# firefly-light.net
KiCad netlist of a schematic drawn in EAGLE
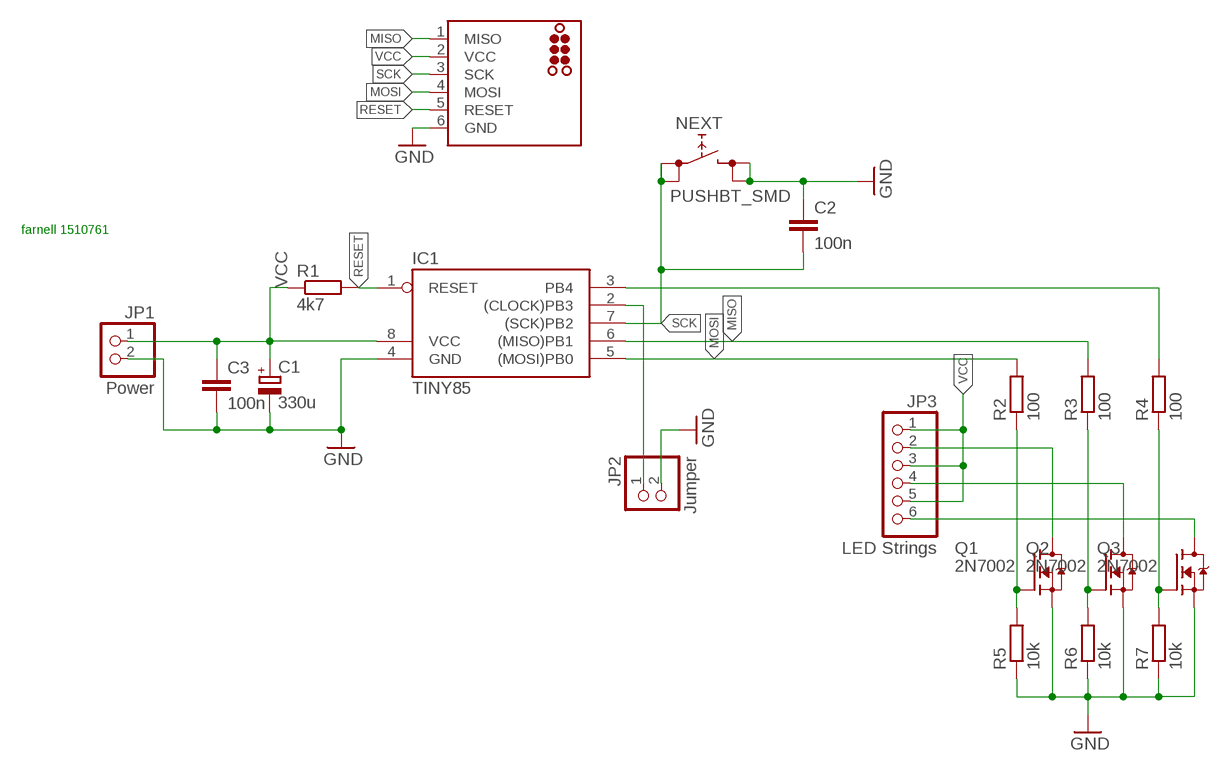
[diagram p0: schematic, sheet 1]

(export (version "E")
  (design (tool "Eeschema 10.0.6"))
  (components
    (comp (ref "C1")
      (value "330u")
      (footprint "eagle-import:E3,5-8")
      (libsource (lib "eagle-import") (part "CPOL-EUE3.5-8"))
    )
    (comp (ref "C2")
      (value "100n")
      (footprint "eagle-import:C0805")
      (libsource (lib "eagle-import") (part "C-EUC0805"))
    )
    (comp (ref "C3")
      (value "100n")
      (footprint "eagle-import:C0805")
      (libsource (lib "eagle-import") (part "C-EUC0805"))
    )
    (comp (ref "IC1")
      (value "TINY85")
      (footprint "eagle-import:SOIC8")
      (libsource (lib "eagle-import") (part "TINY22S"))
    )
    (comp (ref "ISP")
      (value "TC2030-MCP-NL")
      (footprint "eagle-import:TC2030-MCP-NL")
      (libsource (lib "eagle-import") (part "TC2030-MCP-NL"))
    )
    (comp (ref "JP1")
      (value "Power")
      (footprint "eagle-import:1X02")
      (libsource (lib "eagle-import") (part "PINHD-1X2"))
    )
    (comp (ref "JP2")
      (value "Jumper")
      (footprint "eagle-import:1X02")
      (libsource (lib "eagle-import") (part "PINHD-1X2"))
    )
    (comp (ref "JP3")
      (value "LED Strings")
      (footprint "eagle-import:1X06")
      (libsource (lib "eagle-import") (part "PINHD-1X6"))
    )
    (comp (ref "NEXT")
      (value "PUSHBT_SMD")
      (footprint "eagle-import:PUSHBUTTON")
      (libsource (lib "eagle-import") (part "PUSHBT_SMD"))
    )
    (comp (ref "Q1")
      (value "2N7002")
      (footprint "eagle-import:SOT-23")
      (libsource (lib "eagle-import") (part "2N7002"))
    )
    (comp (ref "Q2")
      (value "2N7002")
      (footprint "eagle-import:SOT-23")
      (libsource (lib "eagle-import") (part "2N7002"))
    )
    (comp (ref "Q3")
      (value "2N7002")
      (footprint "eagle-import:SOT-23")
      (libsource (lib "eagle-import") (part "2N7002"))
    )
    (comp (ref "R1")
      (value "4k7")
      (footprint "eagle-import:R0805")
      (libsource (lib "eagle-import") (part "R-EU_R0805"))
    )
    (comp (ref "R2")
      (value "100")
      (footprint "eagle-import:R0805")
      (libsource (lib "eagle-import") (part "R-EU_R0805"))
    )
    (comp (ref "R3")
      (value "100")
      (footprint "eagle-import:R0805")
      (libsource (lib "eagle-import") (part "R-EU_R0805"))
    )
    (comp (ref "R4")
      (value "100")
      (footprint "eagle-import:R0805")
      (libsource (lib "eagle-import") (part "R-EU_R0805"))
    )
    (comp (ref "R5")
      (value "10k")
      (footprint "eagle-import:R0805")
      (libsource (lib "eagle-import") (part "R-EU_R0805"))
    )
    (comp (ref "R6")
      (value "10k")
      (footprint "eagle-import:R0805")
      (libsource (lib "eagle-import") (part "R-EU_R0805"))
    )
    (comp (ref "R7")
      (value "10k")
      (footprint "eagle-import:R0805")
      (libsource (lib "eagle-import") (part "R-EU_R0805"))
    )
  )
  (nets
    (net (code "1") (name "GND") (class "Default")
      (node (ref "C1") (pin "-") (pinfunction "-_-") (pintype "passive"))
      (node (ref "C2") (pin "1") (pinfunction "1_1") (pintype "passive"))
      (node (ref "C3") (pin "2") (pinfunction "2_2") (pintype "passive"))
      (node (ref "IC1") (pin "4") (pinfunction "GND_4") (pintype "power_in"))
      (node (ref "ISP") (pin "6") (pinfunction "GND_6") (pintype "power_in"))
      (node (ref "JP1") (pin "2") (pinfunction "2_2") (pintype "passive"))
      (node (ref "JP2") (pin "2") (pinfunction "2_2") (pintype "passive"))
      (node (ref "NEXT") (pin "B1") (pinfunction "1_B1") (pintype "passive"))
      (node (ref "NEXT") (pin "B2") (pinfunction "1_B2") (pintype "passive"))
      (node (ref "Q1") (pin "2") (pinfunction "S_2") (pintype "passive"))
      (node (ref "Q2") (pin "2") (pinfunction "S_2") (pintype "passive"))
      (node (ref "Q3") (pin "2") (pinfunction "S_2") (pintype "passive"))
      (node (ref "R5") (pin "1") (pinfunction "1_1") (pintype "passive"))
      (node (ref "R6") (pin "1") (pinfunction "1_1") (pintype "passive"))
      (node (ref "R7") (pin "1") (pinfunction "1_1") (pintype "passive"))
    )
    (net (code "2") (name "MISO") (class "Default")
      (node (ref "IC1") (pin "6") (pinfunction "(MISO)PB1_6") (pintype "bidirectional"))
      (node (ref "ISP") (pin "1") (pinfunction "MISO_1") (pintype "input"))
      (node (ref "R3") (pin "2") (pinfunction "2_2") (pintype "passive"))
    )
    (net (code "3") (name "MOSI") (class "Default")
      (node (ref "IC1") (pin "5") (pinfunction "(MOSI)PB0_5") (pintype "bidirectional"))
      (node (ref "ISP") (pin "4") (pinfunction "MOSI_4") (pintype "output"))
      (node (ref "R2") (pin "2") (pinfunction "2_2") (pintype "passive"))
    )
    (net (code "4") (name "Net-(IC1-(CLOCK)PB3)") (class "Default")
      (node (ref "IC1") (pin "2") (pinfunction "(CLOCK)PB3_2") (pintype "bidirectional"))
      (node (ref "JP2") (pin "1") (pinfunction "1_1") (pintype "passive"))
    )
    (net (code "5") (name "Net-(IC1-PB4)") (class "Default")
      (node (ref "IC1") (pin "3") (pinfunction "PB4_3") (pintype "bidirectional"))
      (node (ref "R4") (pin "2") (pinfunction "2_2") (pintype "passive"))
    )
    (net (code "6") (name "Net-(Q1-D)") (class "Default")
      (node (ref "JP3") (pin "2") (pinfunction "2_2") (pintype "passive"))
      (node (ref "Q1") (pin "3") (pinfunction "D_3") (pintype "passive"))
    )
    (net (code "7") (name "Net-(Q1-G)") (class "Default")
      (node (ref "Q1") (pin "1") (pinfunction "G_1") (pintype "passive"))
      (node (ref "R2") (pin "1") (pinfunction "1_1") (pintype "passive"))
      (node (ref "R5") (pin "2") (pinfunction "2_2") (pintype "passive"))
    )
    (net (code "8") (name "Net-(Q2-D)") (class "Default")
      (node (ref "JP3") (pin "4") (pinfunction "4_4") (pintype "passive"))
      (node (ref "Q2") (pin "3") (pinfunction "D_3") (pintype "passive"))
    )
    (net (code "9") (name "Net-(Q2-G)") (class "Default")
      (node (ref "Q2") (pin "1") (pinfunction "G_1") (pintype "passive"))
      (node (ref "R3") (pin "1") (pinfunction "1_1") (pintype "passive"))
      (node (ref "R6") (pin "2") (pinfunction "2_2") (pintype "passive"))
    )
    (net (code "10") (name "Net-(Q3-D)") (class "Default")
      (node (ref "JP3") (pin "6") (pinfunction "6_6") (pintype "passive"))
      (node (ref "Q3") (pin "3") (pinfunction "D_3") (pintype "passive"))
    )
    (net (code "11") (name "Net-(Q3-G)") (class "Default")
      (node (ref "Q3") (pin "1") (pinfunction "G_1") (pintype "passive"))
      (node (ref "R4") (pin "1") (pinfunction "1_1") (pintype "passive"))
      (node (ref "R7") (pin "2") (pinfunction "2_2") (pintype "passive"))
    )
    (net (code "12") (name "RESET") (class "Default")
      (node (ref "IC1") (pin "1") (pinfunction "RESET_1") (pintype "input"))
      (node (ref "ISP") (pin "5") (pinfunction "RESET_5") (pintype "output"))
      (node (ref "R1") (pin "2") (pinfunction "2_2") (pintype "passive"))
    )
    (net (code "13") (name "SCK") (class "Default")
      (node (ref "C2") (pin "2") (pinfunction "2_2") (pintype "passive"))
      (node (ref "IC1") (pin "7") (pinfunction "(SCK)PB2_7") (pintype "bidirectional"))
      (node (ref "ISP") (pin "3") (pinfunction "SCK_3") (pintype "output"))
      (node (ref "NEXT") (pin "A1") (pinfunction "0_A1") (pintype "passive"))
      (node (ref "NEXT") (pin "A2") (pinfunction "0_A2") (pintype "passive"))
    )
    (net (code "14") (name "VCC") (class "Default")
      (node (ref "C1") (pin "+") (pinfunction "+_+") (pintype "passive"))
      (node (ref "C3") (pin "1") (pinfunction "1_1") (pintype "passive"))
      (node (ref "IC1") (pin "8") (pinfunction "VCC_8") (pintype "power_in"))
      (node (ref "ISP") (pin "2") (pinfunction "VCC_2") (pintype "power_in"))
      (node (ref "JP1") (pin "1") (pinfunction "1_1") (pintype "passive"))
      (node (ref "JP3") (pin "1") (pinfunction "1_1") (pintype "passive"))
      (node (ref "JP3") (pin "3") (pinfunction "3_3") (pintype "passive"))
      (node (ref "JP3") (pin "5") (pinfunction "5_5") (pintype "passive"))
      (node (ref "R1") (pin "1") (pinfunction "1_1") (pintype "passive"))
    )
  )
)
